# TouchPad_Demo_v2.net
KiCad netlist of a schematic drawn in EAGLE
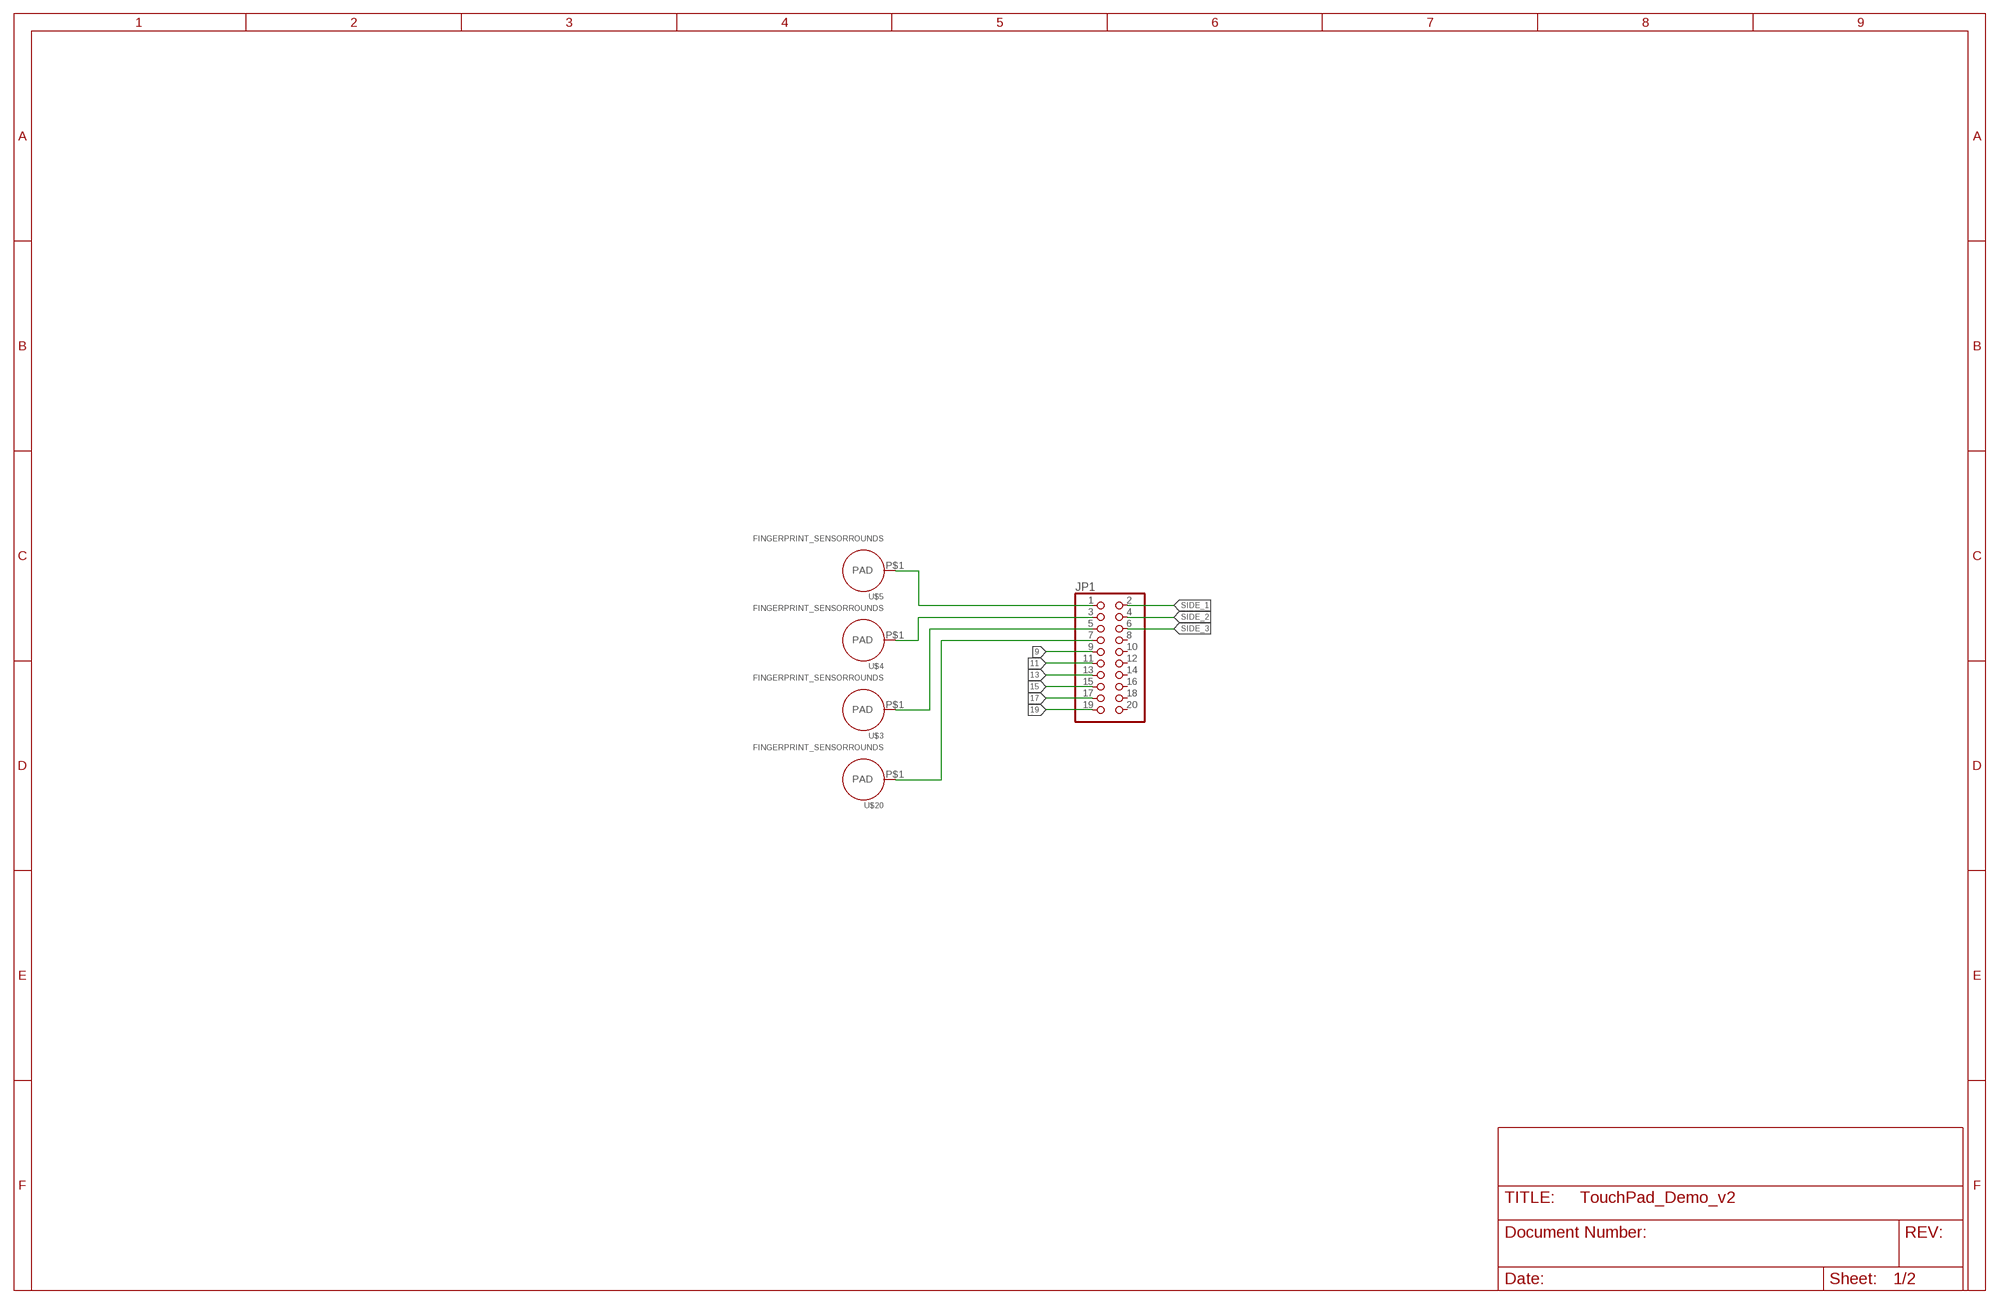
[diagram p0: schematic, sheet 1]

(export (version "E")
  (design (tool "Eeschema 10.0.6"))
  (components
    (comp (ref "JP1")
      (value "HEADER-2X10MOLEX20_SIDE")
      (footprint "eagle-import:MOLEX20_RIGHTANGLE")
      (libsource (lib "eagle-import") (part "HEADER-2X10MOLEX20_SIDE"))
    )
    (comp (ref "U$3")
      (value "FINGERPRINT_SENSORROUNDS")
      (footprint "eagle-import:FINGERPRINT_SENSOR_ROUND")
      (libsource (lib "eagle-import") (part "FINGERPRINT_SENSORROUNDS"))
    )
    (comp (ref "U$4")
      (value "FINGERPRINT_SENSORROUNDS")
      (footprint "eagle-import:FINGERPRINT_SENSOR_ROUND")
      (libsource (lib "eagle-import") (part "FINGERPRINT_SENSORROUNDS"))
    )
    (comp (ref "U$5")
      (value "FINGERPRINT_SENSORROUNDS")
      (footprint "eagle-import:FINGERPRINT_SENSOR_ROUND")
      (libsource (lib "eagle-import") (part "FINGERPRINT_SENSORROUNDS"))
    )
    (comp (ref "U$20")
      (value "FINGERPRINT_SENSORROUNDS")
      (footprint "eagle-import:FINGERPRINT_SENSOR_ROUND")
      (libsource (lib "eagle-import") (part "FINGERPRINT_SENSORROUNDS"))
    )
  )
  (nets
    (net (code "1") (name "9") (class "Default")
      (node (ref "JP1") (pin "9") (pinfunction "9_9") (pintype "passive"))
    )
    (net (code "2") (name "11") (class "Default")
      (node (ref "JP1") (pin "11") (pinfunction "11_11") (pintype "passive"))
    )
    (net (code "3") (name "13") (class "Default")
      (node (ref "JP1") (pin "13") (pinfunction "13_13") (pintype "passive"))
    )
    (net (code "4") (name "15") (class "Default")
      (node (ref "JP1") (pin "15") (pinfunction "15_15") (pintype "passive"))
    )
    (net (code "5") (name "17") (class "Default")
      (node (ref "JP1") (pin "17") (pinfunction "17_17") (pintype "passive"))
    )
    (net (code "6") (name "19") (class "Default")
      (node (ref "JP1") (pin "19") (pinfunction "19_19") (pintype "passive"))
    )
    (net (code "7") (name "Net-(U$3-PAD)") (class "Default")
      (node (ref "JP1") (pin "5") (pinfunction "5_5") (pintype "passive"))
      (node (ref "U$3") (pin "P$1") (pinfunction "PAD_P$1") (pintype "bidirectional"))
    )
    (net (code "8") (name "Net-(U$4-PAD)") (class "Default")
      (node (ref "JP1") (pin "3") (pinfunction "3_3") (pintype "passive"))
      (node (ref "U$4") (pin "P$1") (pinfunction "PAD_P$1") (pintype "bidirectional"))
    )
    (net (code "9") (name "Net-(U$5-PAD)") (class "Default")
      (node (ref "JP1") (pin "1") (pinfunction "1_1") (pintype "passive"))
      (node (ref "U$5") (pin "P$1") (pinfunction "PAD_P$1") (pintype "bidirectional"))
    )
    (net (code "10") (name "Net-(U$20-PAD)") (class "Default")
      (node (ref "JP1") (pin "7") (pinfunction "7_7") (pintype "passive"))
      (node (ref "U$20") (pin "P$1") (pinfunction "PAD_P$1") (pintype "bidirectional"))
    )
    (net (code "11") (name "SIDE_1") (class "Default")
      (node (ref "JP1") (pin "2") (pinfunction "2_2") (pintype "passive"))
    )
    (net (code "12") (name "SIDE_2") (class "Default")
      (node (ref "JP1") (pin "4") (pinfunction "4_4") (pintype "passive"))
    )
    (net (code "13") (name "SIDE_3") (class "Default")
      (node (ref "JP1") (pin "6") (pinfunction "6_6") (pintype "passive"))
    )
    (net (code "14") (name "unconnected-(JP1-Pad8)") (class "Default")
      (node (ref "JP1") (pin "8") (pinfunction "8_8") (pintype "passive"))
    )
    (net (code "15") (name "unconnected-(JP1-Pad10)") (class "Default")
      (node (ref "JP1") (pin "10") (pinfunction "10_10") (pintype "passive"))
    )
    (net (code "16") (name "unconnected-(JP1-Pad12)") (class "Default")
      (node (ref "JP1") (pin "12") (pinfunction "12_12") (pintype "passive"))
    )
    (net (code "17") (name "unconnected-(JP1-Pad14)") (class "Default")
      (node (ref "JP1") (pin "14") (pinfunction "14_14") (pintype "passive"))
    )
    (net (code "18") (name "unconnected-(JP1-Pad16)") (class "Default")
      (node (ref "JP1") (pin "16") (pinfunction "16_16") (pintype "passive"))
    )
    (net (code "19") (name "unconnected-(JP1-Pad18)") (class "Default")
      (node (ref "JP1") (pin "18") (pinfunction "18_18") (pintype "passive"))
    )
    (net (code "20") (name "unconnected-(JP1-Pad20)") (class "Default")
      (node (ref "JP1") (pin "20") (pinfunction "20_20") (pintype "passive"))
    )
  )
)
